# front_DPS.net
KiCad netlist of a schematic drawn in EAGLE
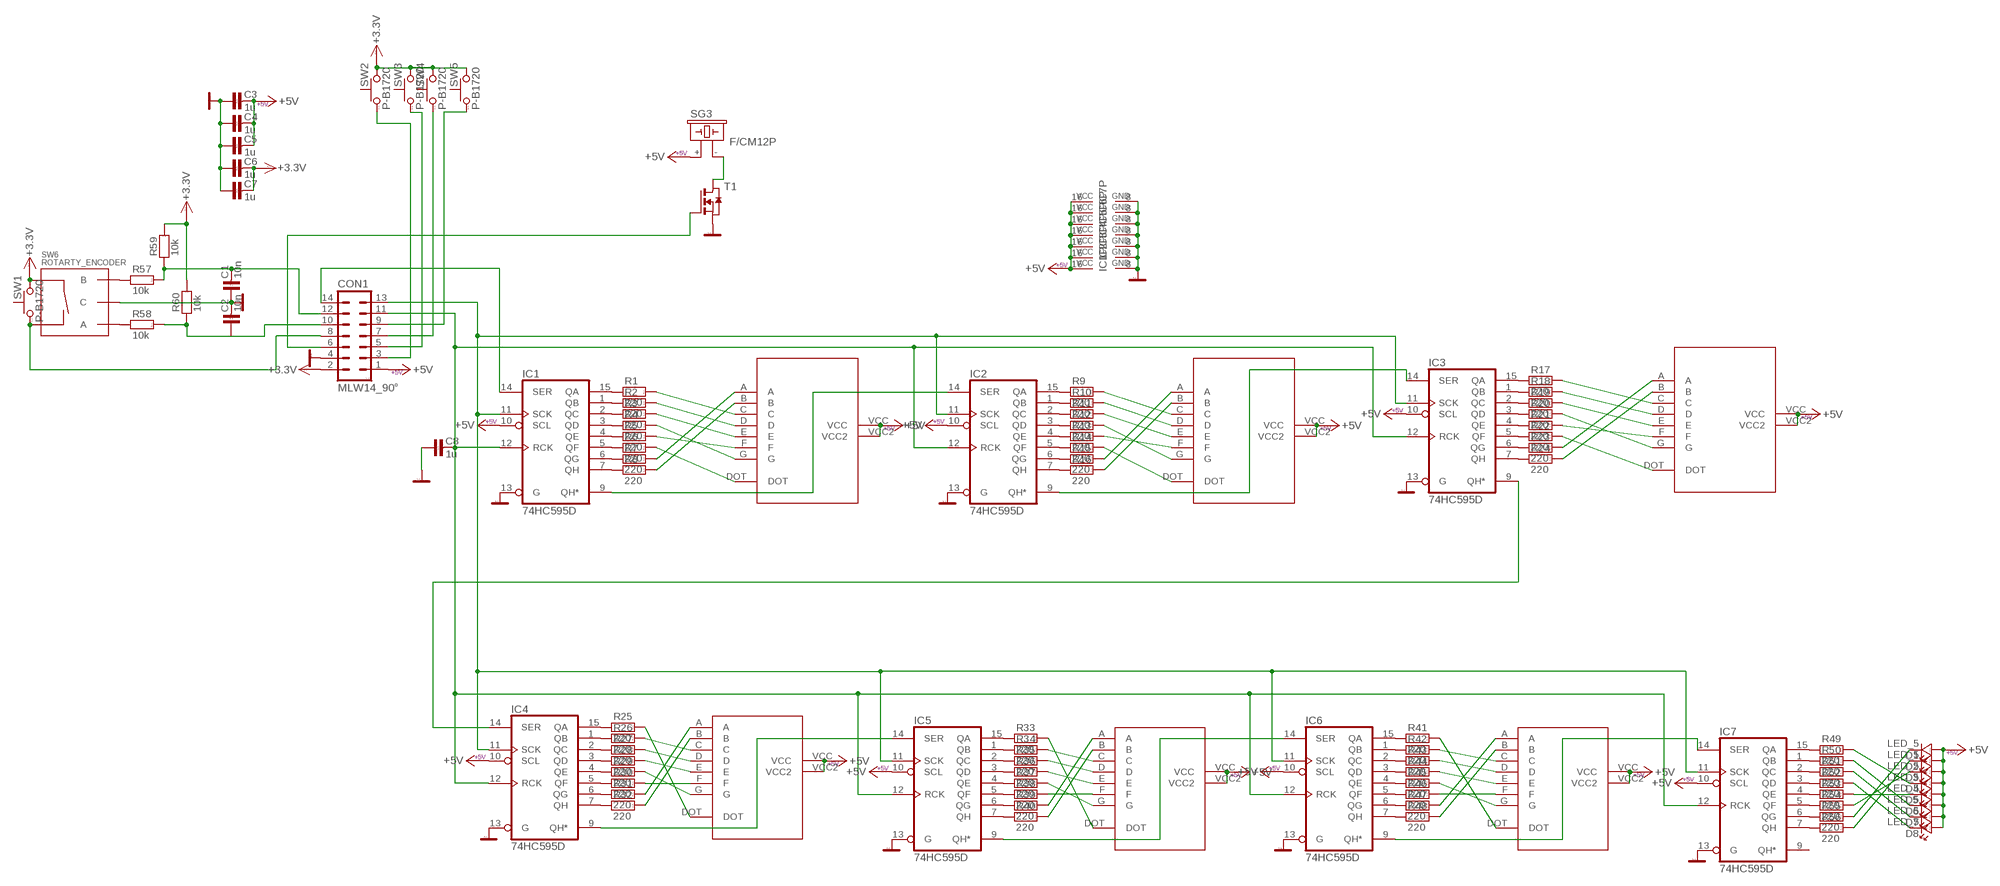
[diagram p0: schematic, sheet 1]

(export (version "E")
  (design (tool "Eeschema 10.0.6"))
  (components
    (comp (ref "C1")
      (value "10n")
      (footprint "eagle-import:1206")
      (libsource (lib "eagle-import") (part "C-KERAMIK_SMD_1206"))
    )
    (comp (ref "C2")
      (value "10n")
      (footprint "eagle-import:1206")
      (libsource (lib "eagle-import") (part "C-KERAMIK_SMD_1206"))
    )
    (comp (ref "C3")
      (value "1u")
      (footprint "eagle-import:1206")
      (libsource (lib "eagle-import") (part "C-KERAMIK_SMD_1206"))
    )
    (comp (ref "C4")
      (value "1u")
      (footprint "eagle-import:1206")
      (libsource (lib "eagle-import") (part "C-KERAMIK_SMD_1206"))
    )
    (comp (ref "C5")
      (value "1u")
      (footprint "eagle-import:1206")
      (libsource (lib "eagle-import") (part "C-KERAMIK_SMD_1206"))
    )
    (comp (ref "C6")
      (value "1u")
      (footprint "eagle-import:1206")
      (libsource (lib "eagle-import") (part "C-KERAMIK_SMD_1206"))
    )
    (comp (ref "C7")
      (value "1u")
      (footprint "eagle-import:1206")
      (libsource (lib "eagle-import") (part "C-KERAMIK_SMD_1206"))
    )
    (comp (ref "C8")
      (value "1u")
      (footprint "eagle-import:1206")
      (libsource (lib "eagle-import") (part "C-KERAMIK_SMD_1206"))
    )
    (comp (ref "CON1")
      (value "MLW14_90°")
      (footprint "eagle-import:MLW14A")
      (libsource (lib "eagle-import") (part "MLW14_90°"))
    )
    (comp (ref "D1")
      (value "LED_5")
      (footprint "eagle-import:LED_5")
      (libsource (lib "eagle-import") (part "LED_5"))
    )
    (comp (ref "D2")
      (value "LED_5")
      (footprint "eagle-import:LED_5")
      (libsource (lib "eagle-import") (part "LED_5"))
    )
    (comp (ref "D3")
      (value "LED_5")
      (footprint "eagle-import:LED_5")
      (libsource (lib "eagle-import") (part "LED_5"))
    )
    (comp (ref "D4")
      (value "LED_5")
      (footprint "eagle-import:LED_5")
      (libsource (lib "eagle-import") (part "LED_5"))
    )
    (comp (ref "D5")
      (value "LED_5")
      (footprint "eagle-import:LED_5")
      (libsource (lib "eagle-import") (part "LED_5"))
    )
    (comp (ref "D6")
      (value "LED_5")
      (footprint "eagle-import:LED_5")
      (libsource (lib "eagle-import") (part "LED_5"))
    )
    (comp (ref "D7")
      (value "LED_5")
      (footprint "eagle-import:LED_5")
      (libsource (lib "eagle-import") (part "LED_5"))
    )
    (comp (ref "D8")
      (value "LED_5")
      (footprint "eagle-import:LED_5")
      (libsource (lib "eagle-import") (part "LED_5"))
    )
    (comp (ref "IC1")
      (value "74HC595D")
      (footprint "eagle-import:SO16")
      (libsource (lib "eagle-import") (part "74595DHC"))
    )
    (comp (ref "IC2")
      (value "74HC595D")
      (footprint "eagle-import:SO16")
      (libsource (lib "eagle-import") (part "74595DHC"))
    )
    (comp (ref "IC3")
      (value "74HC595D")
      (footprint "eagle-import:SO16")
      (libsource (lib "eagle-import") (part "74595DHC"))
    )
    (comp (ref "IC4")
      (value "74HC595D")
      (footprint "eagle-import:SO16")
      (libsource (lib "eagle-import") (part "74595DHC"))
    )
    (comp (ref "IC5")
      (value "74HC595D")
      (footprint "eagle-import:SO16")
      (libsource (lib "eagle-import") (part "74595DHC"))
    )
    (comp (ref "IC6")
      (value "74HC595D")
      (footprint "eagle-import:SO16")
      (libsource (lib "eagle-import") (part "74595DHC"))
    )
    (comp (ref "IC7")
      (value "74HC595D")
      (footprint "eagle-import:SO16")
      (libsource (lib "eagle-import") (part "74595DHC"))
    )
    (comp (ref "R1")
      (value "220")
      (footprint "eagle-import:1206")
      (libsource (lib "eagle-import") (part "R_SMD_1206"))
    )
    (comp (ref "R2")
      (value "220")
      (footprint "eagle-import:1206")
      (libsource (lib "eagle-import") (part "R_SMD_1206"))
    )
    (comp (ref "R3")
      (value "220")
      (footprint "eagle-import:1206")
      (libsource (lib "eagle-import") (part "R_SMD_1206"))
    )
    (comp (ref "R4")
      (value "220")
      (footprint "eagle-import:1206")
      (libsource (lib "eagle-import") (part "R_SMD_1206"))
    )
    (comp (ref "R5")
      (value "220")
      (footprint "eagle-import:1206")
      (libsource (lib "eagle-import") (part "R_SMD_1206"))
    )
    (comp (ref "R6")
      (value "220")
      (footprint "eagle-import:1206")
      (libsource (lib "eagle-import") (part "R_SMD_1206"))
    )
    (comp (ref "R7")
      (value "220")
      (footprint "eagle-import:1206")
      (libsource (lib "eagle-import") (part "R_SMD_1206"))
    )
    (comp (ref "R8")
      (value "220")
      (footprint "eagle-import:1206")
      (libsource (lib "eagle-import") (part "R_SMD_1206"))
    )
    (comp (ref "R9")
      (value "220")
      (footprint "eagle-import:1206")
      (libsource (lib "eagle-import") (part "R_SMD_1206"))
    )
    (comp (ref "R10")
      (value "220")
      (footprint "eagle-import:1206")
      (libsource (lib "eagle-import") (part "R_SMD_1206"))
    )
    (comp (ref "R11")
      (value "220")
      (footprint "eagle-import:1206")
      (libsource (lib "eagle-import") (part "R_SMD_1206"))
    )
    (comp (ref "R12")
      (value "220")
      (footprint "eagle-import:1206")
      (libsource (lib "eagle-import") (part "R_SMD_1206"))
    )
    (comp (ref "R13")
      (value "220")
      (footprint "eagle-import:1206")
      (libsource (lib "eagle-import") (part "R_SMD_1206"))
    )
    (comp (ref "R14")
      (value "220")
      (footprint "eagle-import:1206")
      (libsource (lib "eagle-import") (part "R_SMD_1206"))
    )
    (comp (ref "R15")
      (value "220")
      (footprint "eagle-import:1206")
      (libsource (lib "eagle-import") (part "R_SMD_1206"))
    )
    (comp (ref "R16")
      (value "220")
      (footprint "eagle-import:1206")
      (libsource (lib "eagle-import") (part "R_SMD_1206"))
    )
    (comp (ref "R17")
      (value "220")
      (footprint "eagle-import:1206")
      (libsource (lib "eagle-import") (part "R_SMD_1206"))
    )
    (comp (ref "R18")
      (value "220")
      (footprint "eagle-import:1206")
      (libsource (lib "eagle-import") (part "R_SMD_1206"))
    )
    (comp (ref "R19")
      (value "220")
      (footprint "eagle-import:1206")
      (libsource (lib "eagle-import") (part "R_SMD_1206"))
    )
    (comp (ref "R20")
      (value "220")
      (footprint "eagle-import:1206")
      (libsource (lib "eagle-import") (part "R_SMD_1206"))
    )
    (comp (ref "R21")
      (value "220")
      (footprint "eagle-import:1206")
      (libsource (lib "eagle-import") (part "R_SMD_1206"))
    )
    (comp (ref "R22")
      (value "220")
      (footprint "eagle-import:1206")
      (libsource (lib "eagle-import") (part "R_SMD_1206"))
    )
    (comp (ref "R23")
      (value "220")
      (footprint "eagle-import:1206")
      (libsource (lib "eagle-import") (part "R_SMD_1206"))
    )
    (comp (ref "R24")
      (value "220")
      (footprint "eagle-import:1206")
      (libsource (lib "eagle-import") (part "R_SMD_1206"))
    )
    (comp (ref "R25")
      (value "220")
      (footprint "eagle-import:1206")
      (libsource (lib "eagle-import") (part "R_SMD_1206"))
    )
    (comp (ref "R26")
      (value "220")
      (footprint "eagle-import:1206")
      (libsource (lib "eagle-import") (part "R_SMD_1206"))
    )
    (comp (ref "R27")
      (value "220")
      (footprint "eagle-import:1206")
      (libsource (lib "eagle-import") (part "R_SMD_1206"))
    )
    (comp (ref "R28")
      (value "220")
      (footprint "eagle-import:1206")
      (libsource (lib "eagle-import") (part "R_SMD_1206"))
    )
    (comp (ref "R29")
      (value "220")
      (footprint "eagle-import:1206")
      (libsource (lib "eagle-import") (part "R_SMD_1206"))
    )
    (comp (ref "R30")
      (value "220")
      (footprint "eagle-import:1206")
      (libsource (lib "eagle-import") (part "R_SMD_1206"))
    )
    (comp (ref "R31")
      (value "220")
      (footprint "eagle-import:1206")
      (libsource (lib "eagle-import") (part "R_SMD_1206"))
    )
    (comp (ref "R32")
      (value "220")
      (footprint "eagle-import:1206")
      (libsource (lib "eagle-import") (part "R_SMD_1206"))
    )
    (comp (ref "R33")
      (value "220")
      (footprint "eagle-import:1206")
      (libsource (lib "eagle-import") (part "R_SMD_1206"))
    )
    (comp (ref "R34")
      (value "220")
      (footprint "eagle-import:1206")
      (libsource (lib "eagle-import") (part "R_SMD_1206"))
    )
    (comp (ref "R35")
      (value "220")
      (footprint "eagle-import:1206")
      (libsource (lib "eagle-import") (part "R_SMD_1206"))
    )
    (comp (ref "R36")
      (value "220")
      (footprint "eagle-import:1206")
      (libsource (lib "eagle-import") (part "R_SMD_1206"))
    )
    (comp (ref "R37")
      (value "220")
      (footprint "eagle-import:1206")
      (libsource (lib "eagle-import") (part "R_SMD_1206"))
    )
    (comp (ref "R38")
      (value "220")
      (footprint "eagle-import:1206")
      (libsource (lib "eagle-import") (part "R_SMD_1206"))
    )
    (comp (ref "R39")
      (value "220")
      (footprint "eagle-import:1206")
      (libsource (lib "eagle-import") (part "R_SMD_1206"))
    )
    (comp (ref "R40")
      (value "220")
      (footprint "eagle-import:1206")
      (libsource (lib "eagle-import") (part "R_SMD_1206"))
    )
    (comp (ref "R41")
      (value "220")
      (footprint "eagle-import:1206")
      (libsource (lib "eagle-import") (part "R_SMD_1206"))
    )
    (comp (ref "R42")
      (value "220")
      (footprint "eagle-import:1206")
      (libsource (lib "eagle-import") (part "R_SMD_1206"))
    )
    (comp (ref "R43")
      (value "220")
      (footprint "eagle-import:1206")
      (libsource (lib "eagle-import") (part "R_SMD_1206"))
    )
    (comp (ref "R44")
      (value "220")
      (footprint "eagle-import:1206")
      (libsource (lib "eagle-import") (part "R_SMD_1206"))
    )
    (comp (ref "R45")
      (value "220")
      (footprint "eagle-import:1206")
      (libsource (lib "eagle-import") (part "R_SMD_1206"))
    )
    (comp (ref "R46")
      (value "220")
      (footprint "eagle-import:1206")
      (libsource (lib "eagle-import") (part "R_SMD_1206"))
    )
    (comp (ref "R47")
      (value "220")
      (footprint "eagle-import:1206")
      (libsource (lib "eagle-import") (part "R_SMD_1206"))
    )
    (comp (ref "R48")
      (value "220")
      (footprint "eagle-import:1206")
      (libsource (lib "eagle-import") (part "R_SMD_1206"))
    )
    (comp (ref "R49")
      (value "220")
      (footprint "eagle-import:1206")
      (libsource (lib "eagle-import") (part "R_SMD_1206"))
    )
    (comp (ref "R50")
      (value "220")
      (footprint "eagle-import:1206")
      (libsource (lib "eagle-import") (part "R_SMD_1206"))
    )
    (comp (ref "R51")
      (value "220")
      (footprint "eagle-import:1206")
      (libsource (lib "eagle-import") (part "R_SMD_1206"))
    )
    (comp (ref "R52")
      (value "220")
      (footprint "eagle-import:1206")
      (libsource (lib "eagle-import") (part "R_SMD_1206"))
    )
    (comp (ref "R53")
      (value "220")
      (footprint "eagle-import:1206")
      (libsource (lib "eagle-import") (part "R_SMD_1206"))
    )
    (comp (ref "R54")
      (value "220")
      (footprint "eagle-import:1206")
      (libsource (lib "eagle-import") (part "R_SMD_1206"))
    )
    (comp (ref "R55")
      (value "220")
      (footprint "eagle-import:1206")
      (libsource (lib "eagle-import") (part "R_SMD_1206"))
    )
    (comp (ref "R56")
      (value "220")
      (footprint "eagle-import:1206")
      (libsource (lib "eagle-import") (part "R_SMD_1206"))
    )
    (comp (ref "R57")
      (value "10k")
      (footprint "eagle-import:1206")
      (libsource (lib "eagle-import") (part "R_SMD_1206"))
    )
    (comp (ref "R58")
      (value "10k")
      (footprint "eagle-import:1206")
      (libsource (lib "eagle-import") (part "R_SMD_1206"))
    )
    (comp (ref "R59")
      (value "10k")
      (footprint "eagle-import:1206")
      (libsource (lib "eagle-import") (part "R_SMD_1206"))
    )
    (comp (ref "R60")
      (value "10k")
      (footprint "eagle-import:1206")
      (libsource (lib "eagle-import") (part "R_SMD_1206"))
    )
    (comp (ref "SG3")
      (value "F/CM12P")
      (footprint "eagle-import:F_CM12P")
      (libsource (lib "eagle-import") (part "F/CM12P"))
    )
    (comp (ref "SW1")
      (value "P-B1720")
      (footprint "eagle-import:P-B1720")
      (libsource (lib "eagle-import") (part "P-B1720"))
    )
    (comp (ref "SW2")
      (value "P-B1720")
      (footprint "eagle-import:P-B1720")
      (libsource (lib "eagle-import") (part "P-B1720"))
    )
    (comp (ref "SW3")
      (value "P-B1720")
      (footprint "eagle-import:P-B1720")
      (libsource (lib "eagle-import") (part "P-B1720"))
    )
    (comp (ref "SW4")
      (value "P-B1720")
      (footprint "eagle-import:P-B1720")
      (libsource (lib "eagle-import") (part "P-B1720"))
    )
    (comp (ref "SW5")
      (value "P-B1720")
      (footprint "eagle-import:P-B1720")
      (libsource (lib "eagle-import") (part "P-B1720"))
    )
    (comp (ref "SW6")
      (value "ROTARTY_ENCODER")
      (footprint "eagle-import:ROTARY_ENC_PLAIN")
      (libsource (lib "eagle-import") (part "ROTARTY_ENCODER"))
    )
    (comp (ref "T1")
      (value "NMOSSOT223")
      (footprint "eagle-import:SOT223")
      (libsource (lib "eagle-import") (part "NMOSSOT223"))
    )
    (comp (ref "U$1")
      (value "7-SEGMENT-24X34-ANODE")
      (footprint "eagle-import:7-SEGMENT-24X34")
      (libsource (lib "eagle-import") (part "7-SEGMENT-24X34-ANODE"))
    )
    (comp (ref "U$2")
      (value "7-SEGMENT-24X34-ANODE")
      (footprint "eagle-import:7-SEGMENT-24X34")
      (libsource (lib "eagle-import") (part "7-SEGMENT-24X34-ANODE"))
    )
    (comp (ref "U$3")
      (value "7-SEGMENT-24X34-ANODE")
      (footprint "eagle-import:7-SEGMENT-24X34")
      (libsource (lib "eagle-import") (part "7-SEGMENT-24X34-ANODE"))
    )
    (comp (ref "U$4")
      (value "7-SEGMENT-44X30-ANODE")
      (footprint "eagle-import:7-SEGMENT-44X30")
      (libsource (lib "eagle-import") (part "7-SEGMENT-44X30-ANODE"))
    )
    (comp (ref "U$5")
      (value "7-SEGMENT-44X30-ANODE")
      (footprint "eagle-import:7-SEGMENT-44X30")
      (libsource (lib "eagle-import") (part "7-SEGMENT-44X30-ANODE"))
    )
    (comp (ref "U$6")
      (value "7-SEGMENT-44X30-ANODE")
      (footprint "eagle-import:7-SEGMENT-44X30")
      (libsource (lib "eagle-import") (part "7-SEGMENT-44X30-ANODE"))
    )
  )
  (nets
    (net (code "1") (name "+3.3V") (class "Default")
      (node (ref "C6") (pin "2") (pinfunction "2_2") (pintype "passive"))
      (node (ref "C7") (pin "2") (pinfunction "2_2") (pintype "passive"))
      (node (ref "CON1") (pin "2") (pinfunction "2_2") (pintype "passive"))
      (node (ref "R59") (pin "2") (pinfunction "2_2") (pintype "passive"))
      (node (ref "R60") (pin "2") (pinfunction "2_2") (pintype "passive"))
      (node (ref "SW1") (pin "2") (pinfunction "2_2") (pintype "passive"))
      (node (ref "SW2") (pin "2") (pinfunction "2_2") (pintype "passive"))
      (node (ref "SW3") (pin "2") (pinfunction "2_2") (pintype "passive"))
      (node (ref "SW4") (pin "2") (pinfunction "2_2") (pintype "passive"))
      (node (ref "SW5") (pin "2") (pinfunction "2_2") (pintype "passive"))
      (node (ref "SW6") (pin "SW+") (pinfunction "SW+_SW+") (pintype "bidirectional"))
    )
    (net (code "2") (name "+5V") (class "Default")
      (node (ref "C3") (pin "2") (pinfunction "2_2") (pintype "passive"))
      (node (ref "C4") (pin "2") (pinfunction "2_2") (pintype "passive"))
      (node (ref "C5") (pin "2") (pinfunction "2_2") (pintype "passive"))
      (node (ref "CON1") (pin "1") (pinfunction "1_1") (pintype "passive"))
      (node (ref "D1") (pin "A") (pinfunction "A_A") (pintype "passive"))
      (node (ref "D2") (pin "A") (pinfunction "A_A") (pintype "passive"))
      (node (ref "D3") (pin "A") (pinfunction "A_A") (pintype "passive"))
      (node (ref "D4") (pin "A") (pinfunction "A_A") (pintype "passive"))
      (node (ref "D5") (pin "A") (pinfunction "A_A") (pintype "passive"))
      (node (ref "D6") (pin "A") (pinfunction "A_A") (pintype "passive"))
      (node (ref "D7") (pin "A") (pinfunction "A_A") (pintype "passive"))
      (node (ref "D8") (pin "A") (pinfunction "A_A") (pintype "passive"))
      (node (ref "IC1") (pin "10") (pinfunction "SCL_10") (pintype "input"))
      (node (ref "IC1") (pin "16") (pinfunction "VCC_16") (pintype "power_in"))
      (node (ref "IC2") (pin "10") (pinfunction "SCL_10") (pintype "input"))
      (node (ref "IC2") (pin "16") (pinfunction "VCC_16") (pintype "power_in"))
      (node (ref "IC3") (pin "10") (pinfunction "SCL_10") (pintype "input"))
      (node (ref "IC3") (pin "16") (pinfunction "VCC_16") (pintype "power_in"))
      (node (ref "IC4") (pin "10") (pinfunction "SCL_10") (pintype "input"))
      (node (ref "IC4") (pin "16") (pinfunction "VCC_16") (pintype "power_in"))
      (node (ref "IC5") (pin "10") (pinfunction "SCL_10") (pintype "input"))
      (node (ref "IC5") (pin "16") (pinfunction "VCC_16") (pintype "power_in"))
      (node (ref "IC6") (pin "10") (pinfunction "SCL_10") (pintype "input"))
      (node (ref "IC6") (pin "16") (pinfunction "VCC_16") (pintype "power_in"))
      (node (ref "IC7") (pin "10") (pinfunction "SCL_10") (pintype "input"))
      (node (ref "IC7") (pin "16") (pinfunction "VCC_16") (pintype "power_in"))
      (node (ref "SG3") (pin "+") (pinfunction "1_+") (pintype "passive"))
      (node (ref "U$1") (pin "VCC") (pinfunction "VCC_VCC") (pintype "power_in"))
      (node (ref "U$1") (pin "VCC2") (pinfunction "VCC2_VCC2") (pintype "power_in"))
      (node (ref "U$2") (pin "VCC") (pinfunction "VCC_VCC") (pintype "power_in"))
      (node (ref "U$2") (pin "VCC2") (pinfunction "VCC2_VCC2") (pintype "power_in"))
      (node (ref "U$3") (pin "VCC") (pinfunction "VCC_VCC") (pintype "power_in"))
      (node (ref "U$3") (pin "VCC2") (pinfunction "VCC2_VCC2") (pintype "power_in"))
      (node (ref "U$4") (pin "VCC") (pinfunction "VCC_VCC") (pintype "power_in"))
      (node (ref "U$4") (pin "VCC2") (pinfunction "VCC2_VCC2") (pintype "power_in"))
      (node (ref "U$5") (pin "VCC") (pinfunction "VCC_VCC") (pintype "power_in"))
      (node (ref "U$5") (pin "VCC2") (pinfunction "VCC2_VCC2") (pintype "power_in"))
      (node (ref "U$6") (pin "VCC") (pinfunction "VCC_VCC") (pintype "power_in"))
      (node (ref "U$6") (pin "VCC2") (pinfunction "VCC2_VCC2") (pintype "power_in"))
    )
    (net (code "3") (name "GND") (class "Default")
      (node (ref "C1") (pin "1") (pinfunction "1_1") (pintype "passive"))
      (node (ref "C2") (pin "2") (pinfunction "2_2") (pintype "passive"))
      (node (ref "C3") (pin "1") (pinfunction "1_1") (pintype "passive"))
      (node (ref "C4") (pin "1") (pinfunction "1_1") (pintype "passive"))
      (node (ref "C5") (pin "1") (pinfunction "1_1") (pintype "passive"))
      (node (ref "C6") (pin "1") (pinfunction "1_1") (pintype "passive"))
      (node (ref "C7") (pin "1") (pinfunction "1_1") (pintype "passive"))
      (node (ref "C8") (pin "1") (pinfunction "1_1") (pintype "passive"))
      (node (ref "CON1") (pin "4") (pinfunction "4_4") (pintype "passive"))
      (node (ref "IC1") (pin "13") (pinfunction "G_13") (pintype "input"))
      (node (ref "IC1") (pin "8") (pinfunction "GND_8") (pintype "power_in"))
      (node (ref "IC2") (pin "13") (pinfunction "G_13") (pintype "input"))
      (node (ref "IC2") (pin "8") (pinfunction "GND_8") (pintype "power_in"))
      (node (ref "IC3") (pin "13") (pinfunction "G_13") (pintype "input"))
      (node (ref "IC3") (pin "8") (pinfunction "GND_8") (pintype "power_in"))
      (node (ref "IC4") (pin "13") (pinfunction "G_13") (pintype "input"))
      (node (ref "IC4") (pin "8") (pinfunction "GND_8") (pintype "power_in"))
      (node (ref "IC5") (pin "13") (pinfunction "G_13") (pintype "input"))
      (node (ref "IC5") (pin "8") (pinfunction "GND_8") (pintype "power_in"))
      (node (ref "IC6") (pin "13") (pinfunction "G_13") (pintype "input"))
      (node (ref "IC6") (pin "8") (pinfunction "GND_8") (pintype "power_in"))
      (node (ref "IC7") (pin "13") (pinfunction "G_13") (pintype "input"))
      (node (ref "IC7") (pin "8") (pinfunction "GND_8") (pintype "power_in"))
      (node (ref "SW6") (pin "C") (pinfunction "C_C") (pintype "bidirectional"))
      (node (ref "T1") (pin "3") (pinfunction "S_3") (pintype "passive"))
    )
    (net (code "4") (name "Net-(C1-Pad2)") (class "Default")
      (node (ref "C1") (pin "2") (pinfunction "2_2") (pintype "passive"))
      (node (ref "CON1") (pin "12") (pinfunction "12_12") (pintype "passive"))
      (node (ref "R57") (pin "2") (pinfunction "2_2") (pintype "passive"))
      (node (ref "R59") (pin "1") (pinfunction "1_1") (pintype "passive"))
    )
    (net (code "5") (name "Net-(C2-Pad1)") (class "Default")
      (node (ref "C2") (pin "1") (pinfunction "1_1") (pintype "passive"))
      (node (ref "CON1") (pin "10") (pinfunction "10_10") (pintype "passive"))
      (node (ref "R58") (pin "2") (pinfunction "2_2") (pintype "passive"))
      (node (ref "R60") (pin "1") (pinfunction "1_1") (pintype "passive"))
    )
    (net (code "6") (name "Net-(CON1-Pad3)") (class "Default")
      (node (ref "CON1") (pin "3") (pinfunction "3_3") (pintype "passive"))
      (node (ref "SW2") (pin "1") (pinfunction "1_1") (pintype "passive"))
    )
    (net (code "7") (name "Net-(CON1-Pad5)") (class "Default")
      (node (ref "CON1") (pin "5") (pinfunction "5_5") (pintype "passive"))
      (node (ref "SW3") (pin "1") (pinfunction "1_1") (pintype "passive"))
    )
    (net (code "8") (name "Net-(CON1-Pad7)") (class "Default")
      (node (ref "CON1") (pin "7") (pinfunction "7_7") (pintype "passive"))
      (node (ref "SW4") (pin "1") (pinfunction "1_1") (pintype "passive"))
    )
    (net (code "9") (name "Net-(CON1-Pad8)") (class "Default")
      (node (ref "CON1") (pin "8") (pinfunction "8_8") (pintype "passive"))
      (node (ref "SW1") (pin "1") (pinfunction "1_1") (pintype "passive"))
      (node (ref "SW6") (pin "SW-") (pinfunction "SW-_SW-") (pintype "bidirectional"))
    )
    (net (code "10") (name "Net-(CON1-Pad9)") (class "Default")
      (node (ref "CON1") (pin "9") (pinfunction "9_9") (pintype "passive"))
      (node (ref "SW5") (pin "1") (pinfunction "1_1") (pintype "passive"))
    )
    (net (code "11") (name "Net-(D1-PadK)") (class "Default")
      (node (ref "D1") (pin "K") (pinfunction "K_K") (pintype "passive"))
      (node (ref "R55") (pin "2") (pinfunction "2_2") (pintype "passive"))
    )
    (net (code "12") (name "Net-(D2-PadK)") (class "Default")
      (node (ref "D2") (pin "K") (pinfunction "K_K") (pintype "passive"))
      (node (ref "R56") (pin "2") (pinfunction "2_2") (pintype "passive"))
    )
    (net (code "13") (name "Net-(D3-PadK)") (class "Default")
      (node (ref "D3") (pin "K") (pinfunction "K_K") (pintype "passive"))
      (node (ref "R54") (pin "2") (pinfunction "2_2") (pintype "passive"))
    )
    (net (code "14") (name "Net-(D4-PadK)") (class "Default")
      (node (ref "D4") (pin "K") (pinfunction "K_K") (pintype "passive"))
      (node (ref "R49") (pin "2") (pinfunction "2_2") (pintype "passive"))
    )
    (net (code "15") (name "Net-(D5-PadK)") (class "Default")
      (node (ref "D5") (pin "K") (pinfunction "K_K") (pintype "passive"))
      (node (ref "R53") (pin "2") (pinfunction "2_2") (pintype "passive"))
    )
    (net (code "16") (name "Net-(D6-PadK)") (class "Default")
      (node (ref "D6") (pin "K") (pinfunction "K_K") (pintype "passive"))
      (node (ref "R50") (pin "2") (pinfunction "2_2") (pintype "passive"))
    )
    (net (code "17") (name "Net-(D7-PadK)") (class "Default")
      (node (ref "D7") (pin "K") (pinfunction "K_K") (pintype "passive"))
      (node (ref "R51") (pin "2") (pinfunction "2_2") (pintype "passive"))
    )
    (net (code "18") (name "Net-(D8-PadK)") (class "Default")
      (node (ref "D8") (pin "K") (pinfunction "K_K") (pintype "passive"))
      (node (ref "R52") (pin "2") (pinfunction "2_2") (pintype "passive"))
    )
    (net (code "19") (name "Net-(IC1A-QA)") (class "Default")
      (node (ref "IC1") (pin "15") (pinfunction "QA_15") (pintype "tri_state"))
      (node (ref "R1") (pin "1") (pinfunction "1_1") (pintype "passive"))
    )
    (net (code "20") (name "Net-(IC1A-QB)") (class "Default")
      (node (ref "IC1") (pin "1") (pinfunction "QB_1") (pintype "tri_state"))
      (node (ref "R2") (pin "1") (pinfunction "1_1") (pintype "passive"))
    )
    (net (code "21") (name "Net-(IC1A-QC)") (class "Default")
      (node (ref "IC1") (pin "2") (pinfunction "QC_2") (pintype "tri_state"))
      (node (ref "R3") (pin "1") (pinfunction "1_1") (pintype "passive"))
    )
    (net (code "22") (name "Net-(IC1A-QD)") (class "Default")
      (node (ref "IC1") (pin "3") (pinfunction "QD_3") (pintype "tri_state"))
      (node (ref "R4") (pin "1") (pinfunction "1_1") (pintype "passive"))
    )
    (net (code "23") (name "Net-(IC1A-QE)") (class "Default")
      (node (ref "IC1") (pin "4") (pinfunction "QE_4") (pintype "tri_state"))
      (node (ref "R5") (pin "1") (pinfunction "1_1") (pintype "passive"))
    )
    (net (code "24") (name "Net-(IC1A-QF)") (class "Default")
      (node (ref "IC1") (pin "5") (pinfunction "QF_5") (pintype "tri_state"))
      (node (ref "R6") (pin "1") (pinfunction "1_1") (pintype "passive"))
    )
    (net (code "25") (name "Net-(IC1A-QG)") (class "Default")
      (node (ref "IC1") (pin "6") (pinfunction "QG_6") (pintype "tri_state"))
      (node (ref "R7") (pin "1") (pinfunction "1_1") (pintype "passive"))
    )
    (net (code "26") (name "Net-(IC1A-QH)") (class "Default")
      (node (ref "IC1") (pin "7") (pinfunction "QH_7") (pintype "tri_state"))
      (node (ref "R8") (pin "1") (pinfunction "1_1") (pintype "passive"))
    )
    (net (code "27") (name "Net-(IC1A-QH*)") (class "Default")
      (node (ref "IC1") (pin "9") (pinfunction "QH*_9") (pintype "tri_state"))
      (node (ref "IC2") (pin "14") (pinfunction "SER_14") (pintype "input"))
    )
    (net (code "28") (name "Net-(IC1A-RCK)") (class "Default")
      (node (ref "C8") (pin "2") (pinfunction "2_2") (pintype "passive"))
      (node (ref "CON1") (pin "11") (pinfunction "11_11") (pintype "passive"))
      (node (ref "IC1") (pin "12") (pinfunction "RCK_12") (pintype "input"))
      (node (ref "IC2") (pin "12") (pinfunction "RCK_12") (pintype "input"))
      (node (ref "IC3") (pin "12") (pinfunction "RCK_12") (pintype "input"))
      (node (ref "IC4") (pin "12") (pinfunction "RCK_12") (pintype "input"))
      (node (ref "IC5") (pin "12") (pinfunction "RCK_12") (pintype "input"))
      (node (ref "IC6") (pin "12") (pinfunction "RCK_12") (pintype "input"))
      (node (ref "IC7") (pin "12") (pinfunction "RCK_12") (pintype "input"))
    )
    (net (code "29") (name "Net-(IC1A-SCK)") (class "Default")
      (node (ref "CON1") (pin "13") (pinfunction "13_13") (pintype "passive"))
      (node (ref "IC1") (pin "11") (pinfunction "SCK_11") (pintype "input"))
      (node (ref "IC2") (pin "11") (pinfunction "SCK_11") (pintype "input"))
      (node (ref "IC3") (pin "11") (pinfunction "SCK_11") (pintype "input"))
      (node (ref "IC4") (pin "11") (pinfunction "SCK_11") (pintype "input"))
      (node (ref "IC5") (pin "11") (pinfunction "SCK_11") (pintype "input"))
      (node (ref "IC6") (pin "11") (pinfunction "SCK_11") (pintype "input"))
      (node (ref "IC7") (pin "11") (pinfunction "SCK_11") (pintype "input"))
    )
    (net (code "30") (name "Net-(IC1A-SER)") (class "Default")
      (node (ref "CON1") (pin "14") (pinfunction "14_14") (pintype "passive"))
      (node (ref "IC1") (pin "14") (pinfunction "SER_14") (pintype "input"))
    )
    (net (code "31") (name "Net-(IC2A-QA)") (class "Default")
      (node (ref "IC2") (pin "15") (pinfunction "QA_15") (pintype "tri_state"))
      (node (ref "R9") (pin "1") (pinfunction "1_1") (pintype "passive"))
    )
    (net (code "32") (name "Net-(IC2A-QB)") (class "Default")
      (node (ref "IC2") (pin "1") (pinfunction "QB_1") (pintype "tri_state"))
      (node (ref "R10") (pin "1") (pinfunction "1_1") (pintype "passive"))
    )
    (net (code "33") (name "Net-(IC2A-QC)") (class "Default")
      (node (ref "IC2") (pin "2") (pinfunction "QC_2") (pintype "tri_state"))
      (node (ref "R11") (pin "1") (pinfunction "1_1") (pintype "passive"))
    )
    (net (code "34") (name "Net-(IC2A-QD)") (class "Default")
      (node (ref "IC2") (pin "3") (pinfunction "QD_3") (pintype "tri_state"))
      (node (ref "R12") (pin "1") (pinfunction "1_1") (pintype "passive"))
    )
    (net (code "35") (name "Net-(IC2A-QE)") (class "Default")
      (node (ref "IC2") (pin "4") (pinfunction "QE_4") (pintype "tri_state"))
      (node (ref "R13") (pin "1") (pinfunction "1_1") (pintype "passive"))
    )
    (net (code "36") (name "Net-(IC2A-QF)") (class "Default")
      (node (ref "IC2") (pin "5") (pinfunction "QF_5") (pintype "tri_state"))
      (node (ref "R14") (pin "1") (pinfunction "1_1") (pintype "passive"))
    )
    (net (code "37") (name "Net-(IC2A-QG)") (class "Default")
      (node (ref "IC2") (pin "6") (pinfunction "QG_6") (pintype "tri_state"))
      (node (ref "R15") (pin "1") (pinfunction "1_1") (pintype "passive"))
    )
    (net (code "38") (name "Net-(IC2A-QH)") (class "Default")
      (node (ref "IC2") (pin "7") (pinfunction "QH_7") (pintype "tri_state"))
      (node (ref "R16") (pin "1") (pinfunction "1_1") (pintype "passive"))
    )
    (net (code "39") (name "Net-(IC2A-QH*)") (class "Default")
      (node (ref "IC2") (pin "9") (pinfunction "QH*_9") (pintype "tri_state"))
      (node (ref "IC3") (pin "14") (pinfunction "SER_14") (pintype "input"))
    )
    (net (code "40") (name "Net-(IC3A-QA)") (class "Default")
      (node (ref "IC3") (pin "15") (pinfunction "QA_15") (pintype "tri_state"))
      (node (ref "R17") (pin "1") (pinfunction "1_1") (pintype "passive"))
    )
    (net (code "41") (name "Net-(IC3A-QB)") (class "Default")
      (node (ref "IC3") (pin "1") (pinfunction "QB_1") (pintype "tri_state"))
      (node (ref "R18") (pin "1") (pinfunction "1_1") (pintype "passive"))
    )
    (net (code "42") (name "Net-(IC3A-QC)") (class "Default")
      (node (ref "IC3") (pin "2") (pinfunction "QC_2") (pintype "tri_state"))
      (node (ref "R19") (pin "1") (pinfunction "1_1") (pintype "passive"))
    )
    (net (code "43") (name "Net-(IC3A-QD)") (class "Default")
      (node (ref "IC3") (pin "3") (pinfunction "QD_3") (pintype "tri_state"))
      (node (ref "R20") (pin "1") (pinfunction "1_1") (pintype "passive"))
    )
    (net (code "44") (name "Net-(IC3A-QE)") (class "Default")
      (node (ref "IC3") (pin "4") (pinfunction "QE_4") (pintype "tri_state"))
      (node (ref "R21") (pin "1") (pinfunction "1_1") (pintype "passive"))
    )
    (net (code "45") (name "Net-(IC3A-QF)") (class "Default")
      (node (ref "IC3") (pin "5") (pinfunction "QF_5") (pintype "tri_state"))
      (node (ref "R22") (pin "1") (pinfunction "1_1") (pintype "passive"))
    )
    (net (code "46") (name "Net-(IC3A-QG)") (class "Default")
      (node (ref "IC3") (pin "6") (pinfunction "QG_6") (pintype "tri_state"))
      (node (ref "R23") (pin "1") (pinfunction "1_1") (pintype "passive"))
    )
    (net (code "47") (name "Net-(IC3A-QH)") (class "Default")
      (node (ref "IC3") (pin "7") (pinfunction "QH_7") (pintype "tri_state"))
      (node (ref "R24") (pin "1") (pinfunction "1_1") (pintype "passive"))
    )
    (net (code "48") (name "Net-(IC3A-QH*)") (class "Default")
      (node (ref "IC3") (pin "9") (pinfunction "QH*_9") (pintype "tri_state"))
      (node (ref "IC4") (pin "14") (pinfunction "SER_14") (pintype "input"))
    )
    (net (code "49") (name "Net-(IC4A-QA)") (class "Default")
      (node (ref "IC4") (pin "15") (pinfunction "QA_15") (pintype "tri_state"))
      (node (ref "R25") (pin "1") (pinfunction "1_1") (pintype "passive"))
    )
    (net (code "50") (name "Net-(IC4A-QB)") (class "Default")
      (node (ref "IC4") (pin "1") (pinfunction "QB_1") (pintype "tri_state"))
      (node (ref "R26") (pin "1") (pinfunction "1_1") (pintype "passive"))
    )
    (net (code "51") (name "Net-(IC4A-QC)") (class "Default")
      (node (ref "IC4") (pin "2") (pinfunction "QC_2") (pintype "tri_state"))
      (node (ref "R27") (pin "1") (pinfunction "1_1") (pintype "passive"))
    )
    (net (code "52") (name "Net-(IC4A-QD)") (class "Default")
      (node (ref "IC4") (pin "3") (pinfunction "QD_3") (pintype "tri_state"))
      (node (ref "R28") (pin "1") (pinfunction "1_1") (pintype "passive"))
    )
    (net (code "53") (name "Net-(IC4A-QE)") (class "Default")
      (node (ref "IC4") (pin "4") (pinfunction "QE_4") (pintype "tri_state"))
      (node (ref "R29") (pin "1") (pinfunction "1_1") (pintype "passive"))
    )
    (net (code "54") (name "Net-(IC4A-QF)") (class "Default")
      (node (ref "IC4") (pin "5") (pinfunction "QF_5") (pintype "tri_state"))
      (node (ref "R30") (pin "1") (pinfunction "1_1") (pintype "passive"))
    )
    (net (code "55") (name "Net-(IC4A-QG)") (class "Default")
      (node (ref "IC4") (pin "6") (pinfunction "QG_6") (pintype "tri_state"))
      (node (ref "R31") (pin "1") (pinfunction "1_1") (pintype "passive"))
    )
    (net (code "56") (name "Net-(IC4A-QH)") (class "Default")
      (node (ref "IC4") (pin "7") (pinfunction "QH_7") (pintype "tri_state"))
      (node (ref "R32") (pin "1") (pinfunction "1_1") (pintype "passive"))
    )
    (net (code "57") (name "Net-(IC4A-QH*)") (class "Default")
      (node (ref "IC4") (pin "9") (pinfunction "QH*_9") (pintype "tri_state"))
      (node (ref "IC5") (pin "14") (pinfunction "SER_14") (pintype "input"))
    )
    (net (code "58") (name "Net-(IC5A-QA)") (class "Default")
      (node (ref "IC5") (pin "15") (pinfunction "QA_15") (pintype "tri_state"))
      (node (ref "R33") (pin "1") (pinfunction "1_1") (pintype "passive"))
    )
    (net (code "59") (name "Net-(IC5A-QB)") (class "Default")
      (node (ref "IC5") (pin "1") (pinfunction "QB_1") (pintype "tri_state"))
      (node (ref "R34") (pin "1") (pinfunction "1_1") (pintype "passive"))
    )
    (net (code "60") (name "Net-(IC5A-QC)") (class "Default")
      (node (ref "IC5") (pin "2") (pinfunction "QC_2") (pintype "tri_state"))
      (node (ref "R35") (pin "1") (pinfunction "1_1") (pintype "passive"))
    )
    (net (code "61") (name "Net-(IC5A-QD)") (class "Default")
      (node (ref "IC5") (pin "3") (pinfunction "QD_3") (pintype "tri_state"))
      (node (ref "R36") (pin "1") (pinfunction "1_1") (pintype "passive"))
    )
    (net (code "62") (name "Net-(IC5A-QE)") (class "Default")
      (node (ref "IC5") (pin "4") (pinfunction "QE_4") (pintype "tri_state"))
      (node (ref "R37") (pin "1") (pinfunction "1_1") (pintype "passive"))
    )
    (net (code "63") (name "Net-(IC5A-QF)") (class "Default")
      (node (ref "IC5") (pin "5") (pinfunction "QF_5") (pintype "tri_state"))
      (node (ref "R38") (pin "1") (pinfunction "1_1") (pintype "passive"))
    )
    (net (code "64") (name "Net-(IC5A-QG)") (class "Default")
      (node (ref "IC5") (pin "6") (pinfunction "QG_6") (pintype "tri_state"))
      (node (ref "R39") (pin "1") (pinfunction "1_1") (pintype "passive"))
    )
    (net (code "65") (name "Net-(IC5A-QH)") (class "Default")
      (node (ref "IC5") (pin "7") (pinfunction "QH_7") (pintype "tri_state"))
      (node (ref "R40") (pin "1") (pinfunction "1_1") (pintype "passive"))
    )
    (net (code "66") (name "Net-(IC5A-QH*)") (class "Default")
      (node (ref "IC5") (pin "9") (pinfunction "QH*_9") (pintype "tri_state"))
      (node (ref "IC6") (pin "14") (pinfunction "SER_14") (pintype "input"))
    )
    (net (code "67") (name "Net-(IC6A-QA)") (class "Default")
      (node (ref "IC6") (pin "15") (pinfunction "QA_15") (pintype "tri_state"))
      (node (ref "R41") (pin "1") (pinfunction "1_1") (pintype "passive"))
    )
    (net (code "68") (name "Net-(IC6A-QB)") (class "Default")
      (node (ref "IC6") (pin "1") (pinfunction "QB_1") (pintype "tri_state"))
      (node (ref "R42") (pin "1") (pinfunction "1_1") (pintype "passive"))
    )
    (net (code "69") (name "Net-(IC6A-QC)") (class "Default")
      (node (ref "IC6") (pin "2") (pinfunction "QC_2") (pintype "tri_state"))
      (node (ref "R43") (pin "1") (pinfunction "1_1") (pintype "passive"))
    )
    (net (code "70") (name "Net-(IC6A-QD)") (class "Default")
      (node (ref "IC6") (pin "3") (pinfunction "QD_3") (pintype "tri_state"))
      (node (ref "R44") (pin "1") (pinfunction "1_1") (pintype "passive"))
    )
    (net (code "71") (name "Net-(IC6A-QE)") (class "Default")
      (node (ref "IC6") (pin "4") (pinfunction "QE_4") (pintype "tri_state"))
      (node (ref "R45") (pin "1") (pinfunction "1_1") (pintype "passive"))
    )
    (net (code "72") (name "Net-(IC6A-QF)") (class "Default")
      (node (ref "IC6") (pin "5") (pinfunction "QF_5") (pintype "tri_state"))
      (node (ref "R46") (pin "1") (pinfunction "1_1") (pintype "passive"))
    )
    (net (code "73") (name "Net-(IC6A-QG)") (class "Default")
      (node (ref "IC6") (pin "6") (pinfunction "QG_6") (pintype "tri_state"))
      (node (ref "R47") (pin "1") (pinfunction "1_1") (pintype "passive"))
    )
    (net (code "74") (name "Net-(IC6A-QH)") (class "Default")
      (node (ref "IC6") (pin "7") (pinfunction "QH_7") (pintype "tri_state"))
      (node (ref "R48") (pin "1") (pinfunction "1_1") (pintype "passive"))
    )
    (net (code "75") (name "Net-(IC6A-QH*)") (class "Default")
      (node (ref "IC6") (pin "9") (pinfunction "QH*_9") (pintype "tri_state"))
      (node (ref "IC7") (pin "14") (pinfunction "SER_14") (pintype "input"))
    )
    (net (code "76") (name "Net-(IC7A-QA)") (class "Default")
      (node (ref "IC7") (pin "15") (pinfunction "QA_15") (pintype "tri_state"))
      (node (ref "R49") (pin "1") (pinfunction "1_1") (pintype "passive"))
    )
    (net (code "77") (name "Net-(IC7A-QB)") (class "Default")
      (node (ref "IC7") (pin "1") (pinfunction "QB_1") (pintype "tri_state"))
      (node (ref "R50") (pin "1") (pinfunction "1_1") (pintype "passive"))
    )
    (net (code "78") (name "Net-(IC7A-QC)") (class "Default")
      (node (ref "IC7") (pin "2") (pinfunction "QC_2") (pintype "tri_state"))
      (node (ref "R51") (pin "1") (pinfunction "1_1") (pintype "passive"))
    )
    (net (code "79") (name "Net-(IC7A-QD)") (class "Default")
      (node (ref "IC7") (pin "3") (pinfunction "QD_3") (pintype "tri_state"))
      (node (ref "R52") (pin "1") (pinfunction "1_1") (pintype "passive"))
    )
    (net (code "80") (name "Net-(IC7A-QE)") (class "Default")
      (node (ref "IC7") (pin "4") (pinfunction "QE_4") (pintype "tri_state"))
      (node (ref "R53") (pin "1") (pinfunction "1_1") (pintype "passive"))
    )
    (net (code "81") (name "Net-(IC7A-QF)") (class "Default")
      (node (ref "IC7") (pin "5") (pinfunction "QF_5") (pintype "tri_state"))
      (node (ref "R54") (pin "1") (pinfunction "1_1") (pintype "passive"))
    )
    (net (code "82") (name "Net-(IC7A-QG)") (class "Default")
      (node (ref "IC7") (pin "6") (pinfunction "QG_6") (pintype "tri_state"))
      (node (ref "R55") (pin "1") (pinfunction "1_1") (pintype "passive"))
    )
    (net (code "83") (name "Net-(IC7A-QH)") (class "Default")
      (node (ref "IC7") (pin "7") (pinfunction "QH_7") (pintype "tri_state"))
      (node (ref "R56") (pin "1") (pinfunction "1_1") (pintype "passive"))
    )
    (net (code "84") (name "Net-(R1-Pad2)") (class "Default")
      (node (ref "R1") (pin "2") (pinfunction "2_2") (pintype "passive"))
      (node (ref "U$4") (pin "C") (pinfunction "C_C") (pintype "input"))
    )
    (net (code "85") (name "Net-(R2-Pad2)") (class "Default")
      (node (ref "R2") (pin "2") (pinfunction "2_2") (pintype "passive"))
      (node (ref "U$4") (pin "D") (pinfunction "D_D") (pintype "input"))
    )
    (net (code "86") (name "Net-(R3-Pad2)") (class "Default")
      (node (ref "R3") (pin "2") (pinfunction "2_2") (pintype "passive"))
      (node (ref "U$4") (pin "E") (pinfunction "E_E") (pintype "input"))
    )
    (net (code "87") (name "Net-(R4-Pad2)") (class "Default")
      (node (ref "R4") (pin "2") (pinfunction "2_2") (pintype "passive"))
      (node (ref "U$4") (pin "G") (pinfunction "G_G") (pintype "input"))
    )
    (net (code "88") (name "Net-(R5-Pad2)") (class "Default")
      (node (ref "R5") (pin "2") (pinfunction "2_2") (pintype "passive"))
      (node (ref "U$4") (pin "F") (pinfunction "F_F") (pintype "input"))
    )
    (net (code "89") (name "Net-(R6-Pad2)") (class "Default")
      (node (ref "R6") (pin "2") (pinfunction "2_2") (pintype "passive"))
      (node (ref "U$4") (pin "DOT") (pinfunction "DOT_DOT") (pintype "input"))
    )
    (net (code "90") (name "Net-(R7-Pad2)") (class "Default")
      (node (ref "R7") (pin "2") (pinfunction "2_2") (pintype "passive"))
      (node (ref "U$4") (pin "A") (pinfunction "A_A") (pintype "input"))
    )
    (net (code "91") (name "Net-(R8-Pad2)") (class "Default")
      (node (ref "R8") (pin "2") (pinfunction "2_2") (pintype "passive"))
      (node (ref "U$4") (pin "B") (pinfunction "B_B") (pintype "input"))
    )
    (net (code "92") (name "Net-(R9-Pad2)") (class "Default")
      (node (ref "R9") (pin "2") (pinfunction "2_2") (pintype "passive"))
      (node (ref "U$5") (pin "C") (pinfunction "C_C") (pintype "input"))
    )
    (net (code "93") (name "Net-(R10-Pad2)") (class "Default")
      (node (ref "R10") (pin "2") (pinfunction "2_2") (pintype "passive"))
      (node (ref "U$5") (pin "D") (pinfunction "D_D") (pintype "input"))
    )
    (net (code "94") (name "Net-(R11-Pad2)") (class "Default")
      (node (ref "R11") (pin "2") (pinfunction "2_2") (pintype "passive"))
      (node (ref "U$5") (pin "E") (pinfunction "E_E") (pintype "input"))
    )
    (net (code "95") (name "Net-(R12-Pad2)") (class "Default")
      (node (ref "R12") (pin "2") (pinfunction "2_2") (pintype "passive"))
      (node (ref "U$5") (pin "G") (pinfunction "G_G") (pintype "input"))
    )
    (net (code "96") (name "Net-(R13-Pad2)") (class "Default")
      (node (ref "R13") (pin "2") (pinfunction "2_2") (pintype "passive"))
      (node (ref "U$5") (pin "F") (pinfunction "F_F") (pintype "input"))
    )
    (net (code "97") (name "Net-(R14-Pad2)") (class "Default")
      (node (ref "R14") (pin "2") (pinfunction "2_2") (pintype "passive"))
      (node (ref "U$5") (pin "DOT") (pinfunction "DOT_DOT") (pintype "input"))
    )
    (net (code "98") (name "Net-(R15-Pad2)") (class "Default")
      (node (ref "R15") (pin "2") (pinfunction "2_2") (pintype "passive"))
      (node (ref "U$5") (pin "A") (pinfunction "A_A") (pintype "input"))
    )
    (net (code "99") (name "Net-(R16-Pad2)") (class "Default")
      (node (ref "R16") (pin "2") (pinfunction "2_2") (pintype "passive"))
      (node (ref "U$5") (pin "B") (pinfunction "B_B") (pintype "input"))
    )
    (net (code "100") (name "Net-(R17-Pad2)") (class "Default")
      (node (ref "R17") (pin "2") (pinfunction "2_2") (pintype "passive"))
      (node (ref "U$6") (pin "C") (pinfunction "C_C") (pintype "input"))
    )
    (net (code "101") (name "Net-(R18-Pad2)") (class "Default")
      (node (ref "R18") (pin "2") (pinfunction "2_2") (pintype "passive"))
      (node (ref "U$6") (pin "D") (pinfunction "D_D") (pintype "input"))
    )
    (net (code "102") (name "Net-(R19-Pad2)") (class "Default")
      (node (ref "R19") (pin "2") (pinfunction "2_2") (pintype "passive"))
      (node (ref "U$6") (pin "E") (pinfunction "E_E") (pintype "input"))
    )
    (net (code "103") (name "Net-(R20-Pad2)") (class "Default")
      (node (ref "R20") (pin "2") (pinfunction "2_2") (pintype "passive"))
      (node (ref "U$6") (pin "G") (pinfunction "G_G") (pintype "input"))
    )
    (net (code "104") (name "Net-(R21-Pad2)") (class "Default")
      (node (ref "R21") (pin "2") (pinfunction "2_2") (pintype "passive"))
      (node (ref "U$6") (pin "F") (pinfunction "F_F") (pintype "input"))
    )
    (net (code "105") (name "Net-(R22-Pad2)") (class "Default")
      (node (ref "R22") (pin "2") (pinfunction "2_2") (pintype "passive"))
      (node (ref "U$6") (pin "DOT") (pinfunction "DOT_DOT") (pintype "input"))
    )
    (net (code "106") (name "Net-(R23-Pad2)") (class "Default")
      (node (ref "R23") (pin "2") (pinfunction "2_2") (pintype "passive"))
      (node (ref "U$6") (pin "A") (pinfunction "A_A") (pintype "input"))
    )
    (net (code "107") (name "Net-(R24-Pad2)") (class "Default")
      (node (ref "R24") (pin "2") (pinfunction "2_2") (pintype "passive"))
      (node (ref "U$6") (pin "B") (pinfunction "B_B") (pintype "input"))
    )
    (net (code "108") (name "Net-(R25-Pad2)") (class "Default")
      (node (ref "R25") (pin "2") (pinfunction "2_2") (pintype "passive"))
      (node (ref "U$1") (pin "DOT") (pinfunction "DOT_DOT") (pintype "input"))
    )
    (net (code "109") (name "Net-(R26-Pad2)") (class "Default")
      (node (ref "R26") (pin "2") (pinfunction "2_2") (pintype "passive"))
      (node (ref "U$1") (pin "C") (pinfunction "C_C") (pintype "input"))
    )
    (net (code "110") (name "Net-(R27-Pad2)") (class "Default")
      (node (ref "R27") (pin "2") (pinfunction "2_2") (pintype "passive"))
      (node (ref "U$1") (pin "D") (pinfunction "D_D") (pintype "input"))
    )
    (net (code "111") (name "Net-(R28-Pad2)") (class "Default")
      (node (ref "R28") (pin "2") (pinfunction "2_2") (pintype "passive"))
      (node (ref "U$1") (pin "E") (pinfunction "E_E") (pintype "input"))
    )
    (net (code "112") (name "Net-(R29-Pad2)") (class "Default")
      (node (ref "R29") (pin "2") (pinfunction "2_2") (pintype "passive"))
      (node (ref "U$1") (pin "G") (pinfunction "G_G") (pintype "input"))
    )
    (net (code "113") (name "Net-(R30-Pad2)") (class "Default")
      (node (ref "R30") (pin "2") (pinfunction "2_2") (pintype "passive"))
      (node (ref "U$1") (pin "F") (pinfunction "F_F") (pintype "input"))
    )
    (net (code "114") (name "Net-(R31-Pad2)") (class "Default")
      (node (ref "R31") (pin "2") (pinfunction "2_2") (pintype "passive"))
      (node (ref "U$1") (pin "A") (pinfunction "A_A") (pintype "input"))
    )
    (net (code "115") (name "Net-(R32-Pad2)") (class "Default")
      (node (ref "R32") (pin "2") (pinfunction "2_2") (pintype "passive"))
      (node (ref "U$1") (pin "B") (pinfunction "B_B") (pintype "input"))
    )
    (net (code "116") (name "Net-(R33-Pad2)") (class "Default")
      (node (ref "R33") (pin "2") (pinfunction "2_2") (pintype "passive"))
      (node (ref "U$2") (pin "DOT") (pinfunction "DOT_DOT") (pintype "input"))
    )
    (net (code "117") (name "Net-(R34-Pad2)") (class "Default")
      (node (ref "R34") (pin "2") (pinfunction "2_2") (pintype "passive"))
      (node (ref "U$2") (pin "C") (pinfunction "C_C") (pintype "input"))
    )
    (net (code "118") (name "Net-(R35-Pad2)") (class "Default")
      (node (ref "R35") (pin "2") (pinfunction "2_2") (pintype "passive"))
      (node (ref "U$2") (pin "D") (pinfunction "D_D") (pintype "input"))
    )
    (net (code "119") (name "Net-(R36-Pad2)") (class "Default")
      (node (ref "R36") (pin "2") (pinfunction "2_2") (pintype "passive"))
      (node (ref "U$2") (pin "E") (pinfunction "E_E") (pintype "input"))
    )
    (net (code "120") (name "Net-(R37-Pad2)") (class "Default")
      (node (ref "R37") (pin "2") (pinfunction "2_2") (pintype "passive"))
      (node (ref "U$2") (pin "G") (pinfunction "G_G") (pintype "input"))
    )
    (net (code "121") (name "Net-(R38-Pad2)") (class "Default")
      (node (ref "R38") (pin "2") (pinfunction "2_2") (pintype "passive"))
      (node (ref "U$2") (pin "F") (pinfunction "F_F") (pintype "input"))
    )
    (net (code "122") (name "Net-(R39-Pad2)") (class "Default")
      (node (ref "R39") (pin "2") (pinfunction "2_2") (pintype "passive"))
      (node (ref "U$2") (pin "A") (pinfunction "A_A") (pintype "input"))
    )
    (net (code "123") (name "Net-(R40-Pad2)") (class "Default")
      (node (ref "R40") (pin "2") (pinfunction "2_2") (pintype "passive"))
      (node (ref "U$2") (pin "B") (pinfunction "B_B") (pintype "input"))
    )
    (net (code "124") (name "Net-(R41-Pad2)") (class "Default")
      (node (ref "R41") (pin "2") (pinfunction "2_2") (pintype "passive"))
      (node (ref "U$3") (pin "DOT") (pinfunction "DOT_DOT") (pintype "input"))
    )
    (net (code "125") (name "Net-(R42-Pad2)") (class "Default")
      (node (ref "R42") (pin "2") (pinfunction "2_2") (pintype "passive"))
      (node (ref "U$3") (pin "C") (pinfunction "C_C") (pintype "input"))
    )
    (net (code "126") (name "Net-(R43-Pad2)") (class "Default")
      (node (ref "R43") (pin "2") (pinfunction "2_2") (pintype "passive"))
      (node (ref "U$3") (pin "D") (pinfunction "D_D") (pintype "input"))
    )
    (net (code "127") (name "Net-(R44-Pad2)") (class "Default")
      (node (ref "R44") (pin "2") (pinfunction "2_2") (pintype "passive"))
      (node (ref "U$3") (pin "E") (pinfunction "E_E") (pintype "input"))
    )
    (net (code "128") (name "Net-(R45-Pad2)") (class "Default")
      (node (ref "R45") (pin "2") (pinfunction "2_2") (pintype "passive"))
      (node (ref "U$3") (pin "G") (pinfunction "G_G") (pintype "input"))
    )
    (net (code "129") (name "Net-(R46-Pad2)") (class "Default")
      (node (ref "R46") (pin "2") (pinfunction "2_2") (pintype "passive"))
      (node (ref "U$3") (pin "F") (pinfunction "F_F") (pintype "input"))
    )
    (net (code "130") (name "Net-(R47-Pad2)") (class "Default")
      (node (ref "R47") (pin "2") (pinfunction "2_2") (pintype "passive"))
      (node (ref "U$3") (pin "A") (pinfunction "A_A") (pintype "input"))
    )
    (net (code "131") (name "Net-(R48-Pad2)") (class "Default")
      (node (ref "R48") (pin "2") (pinfunction "2_2") (pintype "passive"))
      (node (ref "U$3") (pin "B") (pinfunction "B_B") (pintype "input"))
    )
    (net (code "132") (name "Net-(R57-Pad1)") (class "Default")
      (node (ref "R57") (pin "1") (pinfunction "1_1") (pintype "passive"))
      (node (ref "SW6") (pin "B") (pinfunction "B_B") (pintype "bidirectional"))
    )
    (net (code "133") (name "Net-(R58-Pad1)") (class "Default")
      (node (ref "R58") (pin "1") (pinfunction "1_1") (pintype "passive"))
      (node (ref "SW6") (pin "A") (pinfunction "A_A") (pintype "bidirectional"))
    )
    (net (code "134") (name "Net-(SG3-2)") (class "Default")
      (node (ref "SG3") (pin "-") (pinfunction "2_-") (pintype "passive"))
      (node (ref "T1") (pin "2") (pinfunction "D_2") (pintype "passive"))
      (node (ref "T1") (pin "4") (pinfunction "D_4") (pintype "passive"))
    )
    (net (code "135") (name "Net-(T1-G)") (class "Default")
      (node (ref "CON1") (pin "6") (pinfunction "6_6") (pintype "passive"))
      (node (ref "T1") (pin "1") (pinfunction "G_1") (pintype "passive"))
    )
    (net (code "136") (name "unconnected-(IC7A-QH*-Pad9)") (class "Default")
      (node (ref "IC7") (pin "9") (pinfunction "QH*_9") (pintype "tri_state"))
    )
    (net (code "137") (name "unconnected-(SW1-Pad3)") (class "Default")
      (node (ref "SW1") (pin "3") (pinfunction "3_3") (pintype "passive"))
    )
    (net (code "138") (name "unconnected-(SW1-Pad4)") (class "Default")
      (node (ref "SW1") (pin "4") (pinfunction "4_4") (pintype "passive"))
    )
    (net (code "139") (name "unconnected-(SW2-Pad3)") (class "Default")
      (node (ref "SW2") (pin "3") (pinfunction "3_3") (pintype "passive"))
    )
    (net (code "140") (name "unconnected-(SW2-Pad4)") (class "Default")
      (node (ref "SW2") (pin "4") (pinfunction "4_4") (pintype "passive"))
    )
    (net (code "141") (name "unconnected-(SW3-Pad3)") (class "Default")
      (node (ref "SW3") (pin "3") (pinfunction "3_3") (pintype "passive"))
    )
    (net (code "142") (name "unconnected-(SW3-Pad4)") (class "Default")
      (node (ref "SW3") (pin "4") (pinfunction "4_4") (pintype "passive"))
    )
    (net (code "143") (name "unconnected-(SW4-Pad3)") (class "Default")
      (node (ref "SW4") (pin "3") (pinfunction "3_3") (pintype "passive"))
    )
    (net (code "144") (name "unconnected-(SW4-Pad4)") (class "Default")
      (node (ref "SW4") (pin "4") (pinfunction "4_4") (pintype "passive"))
    )
    (net (code "145") (name "unconnected-(SW5-Pad3)") (class "Default")
      (node (ref "SW5") (pin "3") (pinfunction "3_3") (pintype "passive"))
    )
    (net (code "146") (name "unconnected-(SW5-Pad4)") (class "Default")
      (node (ref "SW5") (pin "4") (pinfunction "4_4") (pintype "passive"))
    )
  )
)
